# circuit-diagram_easyeda.net
KiCad netlist of a schematic drawn in EasyEDA
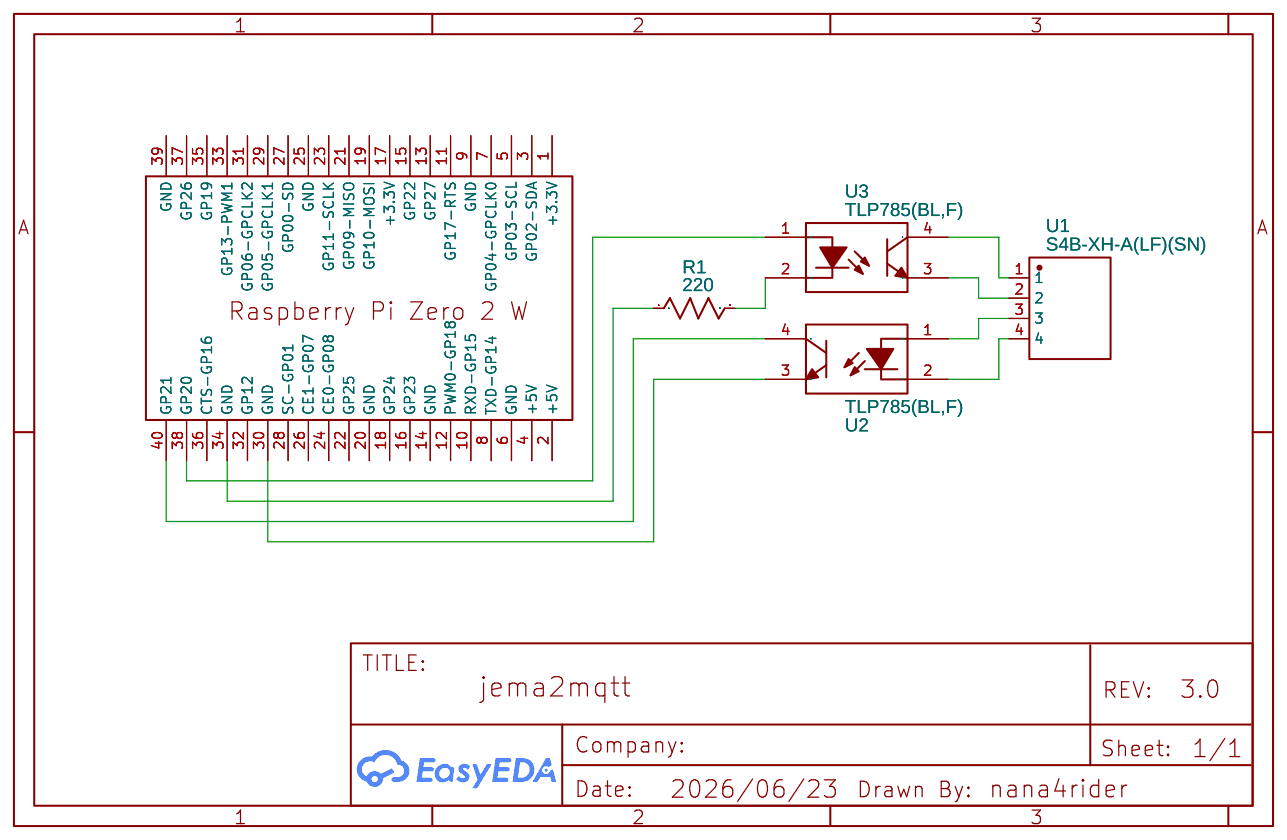
[diagram p0: schematic sheet]

(export (version "E")
  (design (tool "Eeschema 10.0.6"))
  (components
    (comp (ref "R1") (value "220") (libsource (lib "") (part "R_0201_US")))
    (comp (ref "RPI1")
      (value "Raspberry Pi Zero 2 W")
      (fields
        (field (name "Manufacturer Part") "Raspberry Pi Zero WH")
        (field (name "Manufacturer") "Raspberry Pi Foundation")
      )
      (libsource (lib "") (part "Raspberry Pi Zero"))
    )
    (comp (ref "U1")
      (value "S4B-XH-A(LF)(SN)")
      (fields
        (field (name "Manufacturer Part") "B4B-XH-A(LF)(SN)")
        (field (name "Manufacturer") "JST Sales America")
      )
      (libsource (lib "") (part "B4B-XH-A(LF)(SN)"))
    )
    (comp (ref "U2")
      (value "TLP785(BL,F)")
      (fields (field (name "Manufacturer") "TOSHIBA"))
      (libsource (lib "") (part "TLP785(BL,F)"))
    )
    (comp (ref "U3")
      (value "TLP785(BL,F)")
      (fields (field (name "Manufacturer") "TOSHIBA"))
      (libsource (lib "") (part "TLP785(BL,F)_1"))
    )
  )
  (nets
    (net (code "1") (name "Net-(R1-Pad1)") (class "Default")
      (node (ref "R1") (pin "1") (pinfunction "1_1") (pintype "unspecified"))
      (node (ref "RPI1") (pin "34") (pinfunction "GND_34") (pintype "unspecified"))
    )
    (net (code "2") (name "Net-(R1-Pad2)") (class "Default")
      (node (ref "R1") (pin "2") (pinfunction "2_2") (pintype "unspecified"))
      (node (ref "U3") (pin "2") (pinfunction "2_2") (pintype "unspecified"))
    )
    (net (code "3") (name "Net-(RPI1-GND-Pad30)") (class "Default")
      (node (ref "RPI1") (pin "30") (pinfunction "GND_30") (pintype "unspecified"))
      (node (ref "U2") (pin "3") (pinfunction "3_3") (pintype "unspecified"))
    )
    (net (code "4") (name "Net-(RPI1-GP20)") (class "Default")
      (node (ref "RPI1") (pin "38") (pinfunction "GP20_38") (pintype "unspecified"))
      (node (ref "U3") (pin "1") (pinfunction "1_1") (pintype "unspecified"))
    )
    (net (code "5") (name "Net-(RPI1-GP21)") (class "Default")
      (node (ref "RPI1") (pin "40") (pinfunction "GP21_40") (pintype "unspecified"))
      (node (ref "U2") (pin "4") (pinfunction "4_4") (pintype "unspecified"))
    )
    (net (code "6") (name "Net-(U1-Pad1)") (class "Default")
      (node (ref "U1") (pin "1") (pinfunction "1_1") (pintype "unspecified"))
      (node (ref "U3") (pin "4") (pinfunction "4_4") (pintype "unspecified"))
    )
    (net (code "7") (name "Net-(U1-Pad2)") (class "Default")
      (node (ref "U1") (pin "2") (pinfunction "2_2") (pintype "unspecified"))
      (node (ref "U3") (pin "3") (pinfunction "3_3") (pintype "unspecified"))
    )
    (net (code "8") (name "Net-(U1-Pad3)") (class "Default")
      (node (ref "U1") (pin "3") (pinfunction "3_3") (pintype "unspecified"))
      (node (ref "U2") (pin "1") (pinfunction "1_1") (pintype "unspecified"))
    )
    (net (code "9") (name "Net-(U1-Pad4)") (class "Default")
      (node (ref "U1") (pin "4") (pinfunction "4_4") (pintype "unspecified"))
      (node (ref "U2") (pin "2") (pinfunction "2_2") (pintype "unspecified"))
    )
    (net (code "10") (name "unconnected-(RPI1-+3.3V-Pad1)") (class "Default")
      (node (ref "RPI1") (pin "1") (pinfunction "+3.3V_1") (pintype "unspecified"))
    )
    (net (code "11") (name "unconnected-(RPI1-+3.3V-Pad17)") (class "Default")
      (node (ref "RPI1") (pin "17") (pinfunction "+3.3V_17") (pintype "unspecified"))
    )
    (net (code "12") (name "unconnected-(RPI1-+5V-Pad2)") (class "Default")
      (node (ref "RPI1") (pin "2") (pinfunction "+5V_2") (pintype "unspecified"))
    )
    (net (code "13") (name "unconnected-(RPI1-+5V-Pad4)") (class "Default")
      (node (ref "RPI1") (pin "4") (pinfunction "+5V_4") (pintype "unspecified"))
    )
    (net (code "14") (name "unconnected-(RPI1-CE0-GP08-Pad24)") (class "Default")
      (node (ref "RPI1") (pin "24") (pinfunction "CE0-GP08_24") (pintype "unspecified"))
    )
    (net (code "15") (name "unconnected-(RPI1-CE1-GP07-Pad26)") (class "Default")
      (node (ref "RPI1") (pin "26") (pinfunction "CE1-GP07_26") (pintype "unspecified"))
    )
    (net (code "16") (name "unconnected-(RPI1-CTS-GP16-Pad36)") (class "Default")
      (node (ref "RPI1") (pin "36") (pinfunction "CTS-GP16_36") (pintype "unspecified"))
    )
    (net (code "17") (name "unconnected-(RPI1-GND-Pad6)") (class "Default")
      (node (ref "RPI1") (pin "6") (pinfunction "GND_6") (pintype "unspecified"))
    )
    (net (code "18") (name "unconnected-(RPI1-GND-Pad9)") (class "Default")
      (node (ref "RPI1") (pin "9") (pinfunction "GND_9") (pintype "unspecified"))
    )
    (net (code "19") (name "unconnected-(RPI1-GND-Pad14)") (class "Default")
      (node (ref "RPI1") (pin "14") (pinfunction "GND_14") (pintype "unspecified"))
    )
    (net (code "20") (name "unconnected-(RPI1-GND-Pad20)") (class "Default")
      (node (ref "RPI1") (pin "20") (pinfunction "GND_20") (pintype "unspecified"))
    )
    (net (code "21") (name "unconnected-(RPI1-GND-Pad25)") (class "Default")
      (node (ref "RPI1") (pin "25") (pinfunction "GND_25") (pintype "unspecified"))
    )
    (net (code "22") (name "unconnected-(RPI1-GND-Pad39)") (class "Default")
      (node (ref "RPI1") (pin "39") (pinfunction "GND_39") (pintype "unspecified"))
    )
    (net (code "23") (name "unconnected-(RPI1-GP00-SD-Pad27)") (class "Default")
      (node (ref "RPI1") (pin "27") (pinfunction "GP00-SD_27") (pintype "unspecified"))
    )
    (net (code "24") (name "unconnected-(RPI1-GP02-SDA-Pad3)") (class "Default")
      (node (ref "RPI1") (pin "3") (pinfunction "GP02-SDA_3") (pintype "unspecified"))
    )
    (net (code "25") (name "unconnected-(RPI1-GP03-SCL-Pad5)") (class "Default")
      (node (ref "RPI1") (pin "5") (pinfunction "GP03-SCL_5") (pintype "unspecified"))
    )
    (net (code "26") (name "unconnected-(RPI1-GP04-GPCLK0-Pad7)") (class "Default")
      (node (ref "RPI1") (pin "7") (pinfunction "GP04-GPCLK0_7") (pintype "unspecified"))
    )
    (net (code "27") (name "unconnected-(RPI1-GP05-GPCLK1-Pad29)") (class "Default")
      (node (ref "RPI1") (pin "29") (pinfunction "GP05-GPCLK1_29") (pintype "unspecified"))
    )
    (net (code "28") (name "unconnected-(RPI1-GP06-GPCLK2-Pad31)") (class "Default")
      (node (ref "RPI1") (pin "31") (pinfunction "GP06-GPCLK2_31") (pintype "unspecified"))
    )
    (net (code "29") (name "unconnected-(RPI1-GP09-MISO-Pad21)") (class "Default")
      (node (ref "RPI1") (pin "21") (pinfunction "GP09-MISO_21") (pintype "unspecified"))
    )
    (net (code "30") (name "unconnected-(RPI1-GP10-MOSI-Pad19)") (class "Default")
      (node (ref "RPI1") (pin "19") (pinfunction "GP10-MOSI_19") (pintype "unspecified"))
    )
    (net (code "31") (name "unconnected-(RPI1-GP11-SCLK-Pad23)") (class "Default")
      (node (ref "RPI1") (pin "23") (pinfunction "GP11-SCLK_23") (pintype "unspecified"))
    )
    (net (code "32") (name "unconnected-(RPI1-GP12-Pad32)") (class "Default")
      (node (ref "RPI1") (pin "32") (pinfunction "GP12_32") (pintype "unspecified"))
    )
    (net (code "33") (name "unconnected-(RPI1-GP13-PWM1-Pad33)") (class "Default")
      (node (ref "RPI1") (pin "33") (pinfunction "GP13-PWM1_33") (pintype "unspecified"))
    )
    (net (code "34") (name "unconnected-(RPI1-GP17-RTS-Pad11)") (class "Default")
      (node (ref "RPI1") (pin "11") (pinfunction "GP17-RTS_11") (pintype "unspecified"))
    )
    (net (code "35") (name "unconnected-(RPI1-GP19-Pad35)") (class "Default")
      (node (ref "RPI1") (pin "35") (pinfunction "GP19_35") (pintype "unspecified"))
    )
    (net (code "36") (name "unconnected-(RPI1-GP22-Pad15)") (class "Default")
      (node (ref "RPI1") (pin "15") (pinfunction "GP22_15") (pintype "unspecified"))
    )
    (net (code "37") (name "unconnected-(RPI1-GP23-Pad16)") (class "Default")
      (node (ref "RPI1") (pin "16") (pinfunction "GP23_16") (pintype "unspecified"))
    )
    (net (code "38") (name "unconnected-(RPI1-GP24-Pad18)") (class "Default")
      (node (ref "RPI1") (pin "18") (pinfunction "GP24_18") (pintype "unspecified"))
    )
    (net (code "39") (name "unconnected-(RPI1-GP25-Pad22)") (class "Default")
      (node (ref "RPI1") (pin "22") (pinfunction "GP25_22") (pintype "unspecified"))
    )
    (net (code "40") (name "unconnected-(RPI1-GP26-Pad37)") (class "Default")
      (node (ref "RPI1") (pin "37") (pinfunction "GP26_37") (pintype "unspecified"))
    )
    (net (code "41") (name "unconnected-(RPI1-GP27-Pad13)") (class "Default")
      (node (ref "RPI1") (pin "13") (pinfunction "GP27_13") (pintype "unspecified"))
    )
    (net (code "42") (name "unconnected-(RPI1-PWM0-GP18-Pad12)") (class "Default")
      (node (ref "RPI1") (pin "12") (pinfunction "PWM0-GP18_12") (pintype "unspecified"))
    )
    (net (code "43") (name "unconnected-(RPI1-RXD-GP15-Pad10)") (class "Default")
      (node (ref "RPI1") (pin "10") (pinfunction "RXD-GP15_10") (pintype "unspecified"))
    )
    (net (code "44") (name "unconnected-(RPI1-SC-GP01-Pad28)") (class "Default")
      (node (ref "RPI1") (pin "28") (pinfunction "SC-GP01_28") (pintype "unspecified"))
    )
    (net (code "45") (name "unconnected-(RPI1-TXD-GP14-Pad8)") (class "Default")
      (node (ref "RPI1") (pin "8") (pinfunction "TXD-GP14_8") (pintype "unspecified"))
    )
  )
)
